# Res_Cut.net
KiCad netlist of a schematic drawn in EAGLE
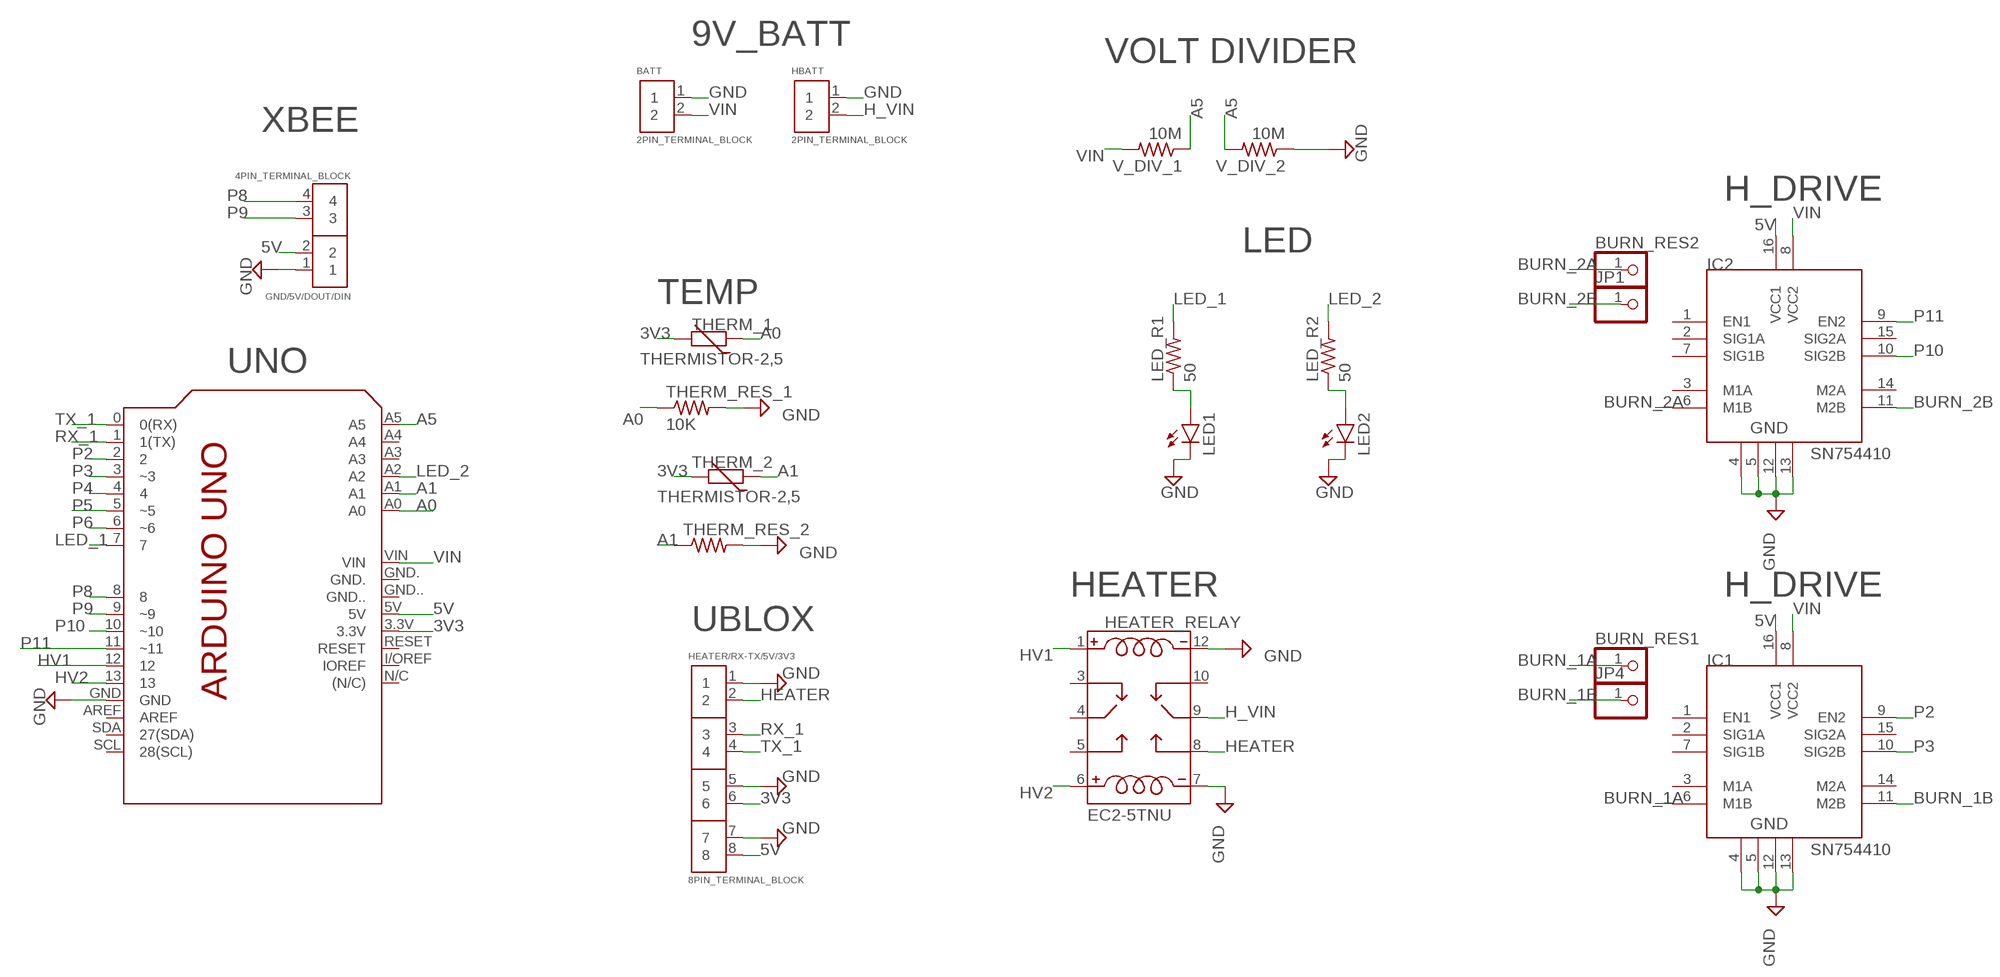
[diagram p0: schematic, sheet 1]

(export (version "E")
  (design (tool "Eeschema 10.0.6"))
  (components
    (comp (ref "BATT")
      (value "2PIN_TERMINAL_BLOCK")
      (footprint "eagle-import:2PIN_TERMINAL_BLOCK")
      (fields
        (field (name "COMMENT") "282834-2")
        (field (name "DIGI-KEY_PART_NUMBER") "A98333-ND")
        (field (name "MF") "TE Connectivity")
      )
      (libsource (lib "eagle-import") (part "2PIN_TERMINAL_BLOCK"))
    )
    (comp (ref "BURN_RES1")
      (value "PINHD-1X1CB")
      (footprint "eagle-import:1X01-CLEANBIG")
      (libsource (lib "eagle-import") (part "PINHD-1X1CB"))
    )
    (comp (ref "BURN_RES2")
      (value "PINHD-1X1CB")
      (footprint "eagle-import:1X01-CLEANBIG")
      (libsource (lib "eagle-import") (part "PINHD-1X1CB"))
    )
    (comp (ref "GND/5V/DOUT/DIN")
      (value "4PIN_TERMINAL_BLOCK")
      (footprint "eagle-import:4PIN_TERMINAL_BLOCK")
      (libsource (lib "eagle-import") (part "4PIN_TERMINAL_BLOCK"))
    )
    (comp (ref "HBATT")
      (value "2PIN_TERMINAL_BLOCK")
      (footprint "eagle-import:2PIN_TERMINAL_BLOCK")
      (fields
        (field (name "COMMENT") "282834-2")
        (field (name "DIGI-KEY_PART_NUMBER") "A98333-ND")
        (field (name "MF") "TE Connectivity")
      )
      (libsource (lib "eagle-import") (part "2PIN_TERMINAL_BLOCK"))
    )
    (comp (ref "HEATER/RX-TX/5V/3V3")
      (value "8PIN_TERMINAL_BLOCK")
      (footprint "eagle-import:8PIN_TERMINAL_BLOCK")
      (libsource (lib "eagle-import") (part "8PIN_TERMINAL_BLOCK"))
    )
    (comp (ref "HEATER_RELAY")
      (value "EC2-5TNU")
      (footprint "eagle-import:RELAY_EC2-5TNU")
      (fields (field (name "MF") "KEMET"))
      (libsource (lib "eagle-import") (part "EC2-5TNU"))
    )
    (comp (ref "IC1")
      (value "SN754410")
      (footprint "eagle-import:DIP16")
      (libsource (lib "eagle-import") (part "SN754410"))
    )
    (comp (ref "IC2")
      (value "SN754410")
      (footprint "eagle-import:DIP16")
      (libsource (lib "eagle-import") (part "SN754410"))
    )
    (comp (ref "JP1")
      (value "PINHD-1X1CB")
      (footprint "eagle-import:1X01-CLEANBIG")
      (libsource (lib "eagle-import") (part "PINHD-1X1CB"))
    )
    (comp (ref "JP4")
      (value "PINHD-1X1CB")
      (footprint "eagle-import:1X01-CLEANBIG")
      (libsource (lib "eagle-import") (part "PINHD-1X1CB"))
    )
    (comp (ref "LED1")
      (value "TLLR4400")
      (footprint "eagle-import:LED3MM")
      (fields (field (name "MF") "VISHAY SEMICONDUCTOR"))
      (libsource (lib "eagle-import") (part "TLLR4400"))
    )
    (comp (ref "LED2")
      (value "TLLR4400")
      (footprint "eagle-import:LED3MM")
      (fields (field (name "MF") "VISHAY SEMICONDUCTOR"))
      (libsource (lib "eagle-import") (part "TLLR4400"))
    )
    (comp (ref "LED_R1")
      (value "50")
      (footprint "eagle-import:0204_7")
      (libsource (lib "eagle-import") (part "resistor_348_R-US_0204/7"))
    )
    (comp (ref "LED_R2")
      (value "50")
      (footprint "eagle-import:0204_7")
      (libsource (lib "eagle-import") (part "resistor_348_R-US_0204/7"))
    )
    (comp (ref "PCB1")
      (value "ARDUINO_UNO")
      (footprint "eagle-import:ARDUINO_UNO")
      (libsource (lib "eagle-import") (part "ARDUINO_UNO"))
    )
    (comp (ref "THERM_1")
      (value "THERMISTOR-2,5")
      (footprint "eagle-import:RS-2,5")
      (libsource (lib "eagle-import") (part "THERMISTOR-2,5"))
    )
    (comp (ref "THERM_2")
      (value "THERMISTOR-2,5")
      (footprint "eagle-import:RS-2,5")
      (libsource (lib "eagle-import") (part "THERMISTOR-2,5"))
    )
    (comp (ref "THERM_RES_1")
      (value "10K")
      (footprint "eagle-import:0204_7")
      (libsource (lib "eagle-import") (part "R-US_0204/7"))
    )
    (comp (ref "THERM_RES_2")
      (value "10K")
      (footprint "eagle-import:0204_7")
      (libsource (lib "eagle-import") (part "R-US_0204/7"))
    )
    (comp (ref "V_DIV_1")
      (value "10M")
      (footprint "eagle-import:0204_7")
      (libsource (lib "eagle-import") (part "resistor_348_R-US_0204/7"))
    )
    (comp (ref "V_DIV_2")
      (value "10M")
      (footprint "eagle-import:0204_7")
      (libsource (lib "eagle-import") (part "resistor_348_R-US_0204/7"))
    )
  )
  (nets
    (net (code "1") (name "/3V3") (class "Default")
      (node (ref "HEATER/RX-TX/5V/3V3") (pin "6") (pinfunction "6_6") (pintype "passive"))
      (node (ref "PCB1") (pin "3.3V") (pinfunction "3.3V_3.3V") (pintype "bidirectional"))
      (node (ref "THERM_1") (pin "2") (pinfunction "2_2") (pintype "passive"))
      (node (ref "THERM_2") (pin "2") (pinfunction "2_2") (pintype "passive"))
    )
    (net (code "2") (name "/5V") (class "Default")
      (node (ref "GND/5V/DOUT/DIN") (pin "2") (pinfunction "2_2") (pintype "passive"))
      (node (ref "HEATER/RX-TX/5V/3V3") (pin "8") (pinfunction "8_8") (pintype "passive"))
      (node (ref "IC1") (pin "16") (pinfunction "VCC1_16") (pintype "power_in"))
      (node (ref "IC2") (pin "16") (pinfunction "VCC1_16") (pintype "power_in"))
      (node (ref "PCB1") (pin "5V") (pinfunction "5V_5V") (pintype "bidirectional"))
    )
    (net (code "3") (name "/A0") (class "Default")
      (node (ref "PCB1") (pin "A0") (pinfunction "A0_A0") (pintype "bidirectional"))
      (node (ref "THERM_1") (pin "1") (pinfunction "1_1") (pintype "passive"))
      (node (ref "THERM_RES_1") (pin "1") (pinfunction "1_1") (pintype "passive"))
    )
    (net (code "4") (name "/A1") (class "Default")
      (node (ref "PCB1") (pin "A1") (pinfunction "A1_A1") (pintype "bidirectional"))
      (node (ref "THERM_2") (pin "1") (pinfunction "1_1") (pintype "passive"))
      (node (ref "THERM_RES_2") (pin "1") (pinfunction "1_1") (pintype "passive"))
    )
    (net (code "5") (name "/A5") (class "Default")
      (node (ref "PCB1") (pin "A5") (pinfunction "A5_A5") (pintype "bidirectional"))
      (node (ref "V_DIV_1") (pin "1") (pinfunction "1_1") (pintype "passive"))
      (node (ref "V_DIV_2") (pin "2") (pinfunction "2_2") (pintype "passive"))
    )
    (net (code "6") (name "/BURN_1A") (class "Default")
      (node (ref "BURN_RES1") (pin "1") (pinfunction "1_1") (pintype "passive"))
      (node (ref "IC1") (pin "6") (pinfunction "M1B_6") (pintype "bidirectional"))
    )
    (net (code "7") (name "/BURN_1B") (class "Default")
      (node (ref "IC1") (pin "11") (pinfunction "M2B_11") (pintype "bidirectional"))
      (node (ref "JP4") (pin "1") (pinfunction "1_1") (pintype "passive"))
    )
    (net (code "8") (name "/BURN_2A") (class "Default")
      (node (ref "BURN_RES2") (pin "1") (pinfunction "1_1") (pintype "passive"))
      (node (ref "IC2") (pin "6") (pinfunction "M1B_6") (pintype "bidirectional"))
    )
    (net (code "9") (name "/BURN_2B") (class "Default")
      (node (ref "IC2") (pin "11") (pinfunction "M2B_11") (pintype "bidirectional"))
      (node (ref "JP1") (pin "1") (pinfunction "1_1") (pintype "passive"))
    )
    (net (code "10") (name "/HEATER") (class "Default")
      (node (ref "HEATER/RX-TX/5V/3V3") (pin "2") (pinfunction "2_2") (pintype "passive"))
      (node (ref "HEATER_RELAY") (pin "8") (pinfunction "NO_8") (pintype "passive"))
    )
    (net (code "11") (name "/HV1") (class "Default")
      (node (ref "HEATER_RELAY") (pin "1") (pinfunction "C1_1") (pintype "passive"))
      (node (ref "PCB1") (pin "12") (pinfunction "12_12") (pintype "bidirectional"))
    )
    (net (code "12") (name "/HV2") (class "Default")
      (node (ref "HEATER_RELAY") (pin "6") (pinfunction "C3_6") (pintype "passive"))
      (node (ref "PCB1") (pin "13") (pinfunction "13_13") (pintype "bidirectional"))
    )
    (net (code "13") (name "/H_VIN") (class "Default")
      (node (ref "HBATT") (pin "2") (pinfunction "2_2") (pintype "passive"))
      (node (ref "HEATER_RELAY") (pin "9") (pinfunction "M_9") (pintype "passive"))
    )
    (net (code "14") (name "/LED_1") (class "Default")
      (node (ref "LED_R1") (pin "2") (pinfunction "2_2") (pintype "passive"))
      (node (ref "PCB1") (pin "7") (pinfunction "7_7") (pintype "bidirectional"))
    )
    (net (code "15") (name "/LED_2") (class "Default")
      (node (ref "LED_R2") (pin "2") (pinfunction "2_2") (pintype "passive"))
      (node (ref "PCB1") (pin "A2") (pinfunction "A2_A2") (pintype "bidirectional"))
    )
    (net (code "16") (name "/P2") (class "Default")
      (node (ref "IC1") (pin "9") (pinfunction "EN2_9") (pintype "bidirectional"))
      (node (ref "PCB1") (pin "2") (pinfunction "2_2") (pintype "bidirectional"))
    )
    (net (code "17") (name "/P3") (class "Default")
      (node (ref "IC1") (pin "10") (pinfunction "SIG2B_10") (pintype "bidirectional"))
      (node (ref "PCB1") (pin "3") (pinfunction "~{3}_3") (pintype "bidirectional"))
    )
    (net (code "18") (name "/P4") (class "Default")
      (node (ref "PCB1") (pin "4") (pinfunction "4_4") (pintype "bidirectional"))
    )
    (net (code "19") (name "/P5") (class "Default")
      (node (ref "PCB1") (pin "5") (pinfunction "~{5}_5") (pintype "bidirectional"))
    )
    (net (code "20") (name "/P6") (class "Default")
      (node (ref "PCB1") (pin "6") (pinfunction "~{6}_6") (pintype "bidirectional"))
    )
    (net (code "21") (name "/P8") (class "Default")
      (node (ref "GND/5V/DOUT/DIN") (pin "4") (pinfunction "4_4") (pintype "passive"))
      (node (ref "PCB1") (pin "8") (pinfunction "8_8") (pintype "bidirectional"))
    )
    (net (code "22") (name "/P9") (class "Default")
      (node (ref "GND/5V/DOUT/DIN") (pin "3") (pinfunction "3_3") (pintype "passive"))
      (node (ref "PCB1") (pin "9") (pinfunction "~{9}_9") (pintype "bidirectional"))
    )
    (net (code "23") (name "/P10") (class "Default")
      (node (ref "IC2") (pin "10") (pinfunction "SIG2B_10") (pintype "bidirectional"))
      (node (ref "PCB1") (pin "10") (pinfunction "~{10}_10") (pintype "bidirectional"))
    )
    (net (code "24") (name "/P11") (class "Default")
      (node (ref "IC2") (pin "9") (pinfunction "EN2_9") (pintype "bidirectional"))
      (node (ref "PCB1") (pin "11") (pinfunction "~{11}_11") (pintype "bidirectional"))
    )
    (net (code "25") (name "/RX_1") (class "Default")
      (node (ref "HEATER/RX-TX/5V/3V3") (pin "3") (pinfunction "3_3") (pintype "passive"))
      (node (ref "PCB1") (pin "1") (pinfunction "1(TX)_1") (pintype "bidirectional"))
    )
    (net (code "26") (name "/TX_1") (class "Default")
      (node (ref "HEATER/RX-TX/5V/3V3") (pin "4") (pinfunction "4_4") (pintype "passive"))
      (node (ref "PCB1") (pin "0") (pinfunction "0(RX)_0") (pintype "bidirectional"))
    )
    (net (code "27") (name "/VIN") (class "Default")
      (node (ref "BATT") (pin "2") (pinfunction "2_2") (pintype "passive"))
      (node (ref "IC1") (pin "8") (pinfunction "VCC2_8") (pintype "power_in"))
      (node (ref "IC2") (pin "8") (pinfunction "VCC2_8") (pintype "power_in"))
      (node (ref "PCB1") (pin "VIN") (pinfunction "VIN_VIN") (pintype "bidirectional"))
      (node (ref "V_DIV_1") (pin "2") (pinfunction "2_2") (pintype "passive"))
    )
    (net (code "28") (name "GND") (class "Default")
      (node (ref "BATT") (pin "1") (pinfunction "1_1") (pintype "passive"))
      (node (ref "GND/5V/DOUT/DIN") (pin "1") (pinfunction "1_1") (pintype "passive"))
      (node (ref "HBATT") (pin "1") (pinfunction "1_1") (pintype "passive"))
      (node (ref "HEATER/RX-TX/5V/3V3") (pin "1") (pinfunction "1_1") (pintype "passive"))
      (node (ref "HEATER/RX-TX/5V/3V3") (pin "5") (pinfunction "5_5") (pintype "passive"))
      (node (ref "HEATER/RX-TX/5V/3V3") (pin "7") (pinfunction "7_7") (pintype "passive"))
      (node (ref "HEATER_RELAY") (pin "12") (pinfunction "C2_12") (pintype "passive"))
      (node (ref "HEATER_RELAY") (pin "7") (pinfunction "C4_7") (pintype "passive"))
      (node (ref "IC1") (pin "12") (pinfunction "P12_12") (pintype "power_in"))
      (node (ref "IC1") (pin "13") (pinfunction "P13_13") (pintype "power_in"))
      (node (ref "IC1") (pin "4") (pinfunction "P4_4") (pintype "power_in"))
      (node (ref "IC1") (pin "5") (pinfunction "P5_5") (pintype "power_in"))
      (node (ref "IC2") (pin "12") (pinfunction "P12_12") (pintype "power_in"))
      (node (ref "IC2") (pin "13") (pinfunction "P13_13") (pintype "power_in"))
      (node (ref "IC2") (pin "4") (pinfunction "P4_4") (pintype "power_in"))
      (node (ref "IC2") (pin "5") (pinfunction "P5_5") (pintype "power_in"))
      (node (ref "LED1") (pin "K") (pinfunction "C_K") (pintype "passive"))
      (node (ref "LED2") (pin "K") (pinfunction "C_K") (pintype "passive"))
      (node (ref "PCB1") (pin "GND") (pinfunction "GND_GND") (pintype "bidirectional"))
      (node (ref "THERM_RES_1") (pin "2") (pinfunction "2_2") (pintype "passive"))
      (node (ref "THERM_RES_2") (pin "2") (pinfunction "2_2") (pintype "passive"))
      (node (ref "V_DIV_2") (pin "1") (pinfunction "1_1") (pintype "passive"))
    )
    (net (code "29") (name "Net-(LED1-PadA)") (class "Default")
      (node (ref "LED1") (pin "A") (pinfunction "A_A") (pintype "passive"))
      (node (ref "LED_R1") (pin "1") (pinfunction "1_1") (pintype "passive"))
    )
    (net (code "30") (name "Net-(LED2-PadA)") (class "Default")
      (node (ref "LED2") (pin "A") (pinfunction "A_A") (pintype "passive"))
      (node (ref "LED_R2") (pin "1") (pinfunction "1_1") (pintype "passive"))
    )
    (net (code "31") (name "unconnected-(HEATER_RELAY-M1-Pad4)") (class "Default")
      (node (ref "HEATER_RELAY") (pin "4") (pinfunction "M1_4") (pintype "passive"))
    )
    (net (code "32") (name "unconnected-(HEATER_RELAY-NC-Pad10)") (class "Default")
      (node (ref "HEATER_RELAY") (pin "10") (pinfunction "NC_10") (pintype "passive"))
    )
    (net (code "33") (name "unconnected-(HEATER_RELAY-NC1-Pad3)") (class "Default")
      (node (ref "HEATER_RELAY") (pin "3") (pinfunction "NC1_3") (pintype "passive"))
    )
    (net (code "34") (name "unconnected-(HEATER_RELAY-NO1-Pad5)") (class "Default")
      (node (ref "HEATER_RELAY") (pin "5") (pinfunction "NO1_5") (pintype "passive"))
    )
    (net (code "35") (name "unconnected-(IC1-EN1-Pad1)") (class "Default")
      (node (ref "IC1") (pin "1") (pinfunction "EN1_1") (pintype "bidirectional"))
    )
    (net (code "36") (name "unconnected-(IC1-M1A-Pad3)") (class "Default")
      (node (ref "IC1") (pin "3") (pinfunction "M1A_3") (pintype "bidirectional"))
    )
    (net (code "37") (name "unconnected-(IC1-M2A-Pad14)") (class "Default")
      (node (ref "IC1") (pin "14") (pinfunction "M2A_14") (pintype "bidirectional"))
    )
    (net (code "38") (name "unconnected-(IC1-SIG1A-Pad2)") (class "Default")
      (node (ref "IC1") (pin "2") (pinfunction "SIG1A_2") (pintype "bidirectional"))
    )
    (net (code "39") (name "unconnected-(IC1-SIG1B-Pad7)") (class "Default")
      (node (ref "IC1") (pin "7") (pinfunction "SIG1B_7") (pintype "bidirectional"))
    )
    (net (code "40") (name "unconnected-(IC1-SIG2A-Pad15)") (class "Default")
      (node (ref "IC1") (pin "15") (pinfunction "SIG2A_15") (pintype "bidirectional"))
    )
    (net (code "41") (name "unconnected-(IC2-EN1-Pad1)") (class "Default")
      (node (ref "IC2") (pin "1") (pinfunction "EN1_1") (pintype "bidirectional"))
    )
    (net (code "42") (name "unconnected-(IC2-M1A-Pad3)") (class "Default")
      (node (ref "IC2") (pin "3") (pinfunction "M1A_3") (pintype "bidirectional"))
    )
    (net (code "43") (name "unconnected-(IC2-M2A-Pad14)") (class "Default")
      (node (ref "IC2") (pin "14") (pinfunction "M2A_14") (pintype "bidirectional"))
    )
    (net (code "44") (name "unconnected-(IC2-SIG1A-Pad2)") (class "Default")
      (node (ref "IC2") (pin "2") (pinfunction "SIG1A_2") (pintype "bidirectional"))
    )
    (net (code "45") (name "unconnected-(IC2-SIG1B-Pad7)") (class "Default")
      (node (ref "IC2") (pin "7") (pinfunction "SIG1B_7") (pintype "bidirectional"))
    )
    (net (code "46") (name "unconnected-(IC2-SIG2A-Pad15)") (class "Default")
      (node (ref "IC2") (pin "15") (pinfunction "SIG2A_15") (pintype "bidirectional"))
    )
    (net (code "47") (name "unconnected-(PCB1-(N{slash}C)-PadN{slash}C)") (class "Default")
      (node (ref "PCB1") (pin "N/C") (pinfunction "(N/C)_N/C") (pintype "bidirectional"))
    )
    (net (code "48") (name "unconnected-(PCB1-27(SDA)-PadSDA)") (class "Default")
      (node (ref "PCB1") (pin "SDA") (pinfunction "27(SDA)_SDA") (pintype "bidirectional"))
    )
    (net (code "49") (name "unconnected-(PCB1-28(SCL)-PadSCL)") (class "Default")
      (node (ref "PCB1") (pin "SCL") (pinfunction "28(SCL)_SCL") (pintype "bidirectional"))
    )
    (net (code "50") (name "unconnected-(PCB1-IOREF-PadI{slash}OREF)") (class "Default")
      (node (ref "PCB1") (pin "I/OREF") (pinfunction "IOREF_I/OREF") (pintype "bidirectional"))
    )
    (net (code "51") (name "unconnected-(PCB1-PadA3)") (class "Default")
      (node (ref "PCB1") (pin "A3") (pinfunction "A3_A3") (pintype "bidirectional"))
    )
    (net (code "52") (name "unconnected-(PCB1-PadA4)") (class "Default")
      (node (ref "PCB1") (pin "A4") (pinfunction "A4_A4") (pintype "bidirectional"))
    )
    (net (code "53") (name "unconnected-(PCB1-PadAREF)") (class "Default")
      (node (ref "PCB1") (pin "AREF") (pinfunction "AREF_AREF") (pintype "bidirectional"))
    )
    (net (code "54") (name "unconnected-(PCB1-PadGND.)") (class "Default")
      (node (ref "PCB1") (pin "GND.") (pinfunction "GND._GND.") (pintype "bidirectional"))
    )
    (net (code "55") (name "unconnected-(PCB1-PadGND..)") (class "Default")
      (node (ref "PCB1") (pin "GND..") (pinfunction "GND.._GND..") (pintype "bidirectional"))
    )
    (net (code "56") (name "unconnected-(PCB1-PadRESET)") (class "Default")
      (node (ref "PCB1") (pin "RESET") (pinfunction "RESET_RESET") (pintype "bidirectional"))
    )
  )
)
